# SCH_airocat_2023-06-29.net
KiCad netlist of a schematic drawn in EasyEDA
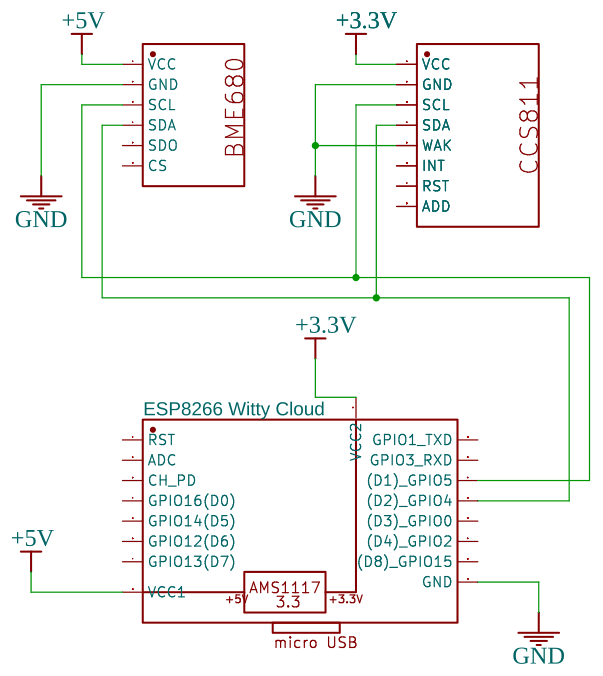
[diagram p0: schematic sheet]

(export (version "E")
  (design (tool "Eeschema 10.0.6"))
  (components
    (comp (ref "U1") (value "BME680") (libsource (lib "") (part "BME680")))
    (comp (ref "U2") (value "CCS811") (libsource (lib "") (part "CCS811")))
    (comp (ref "U3") (value "ESP8266 Witty Cloud") (libsource (lib "") (part "ESP8266 Witty Cloud")))
  )
  (nets
    (net (code "1") (name "+3.3V") (class "Default")
      (node (ref "U2") (pin "1") (pinfunction "VCC_1") (pintype "unspecified"))
      (node (ref "U3") (pin "17") (pinfunction "VCC2_17") (pintype "unspecified"))
    )
    (net (code "2") (name "+5V") (class "Default")
      (node (ref "U1") (pin "1") (pinfunction "VCC_1") (pintype "unspecified"))
      (node (ref "U3") (pin "8") (pinfunction "VCC1_8") (pintype "unspecified"))
    )
    (net (code "3") (name "GND") (class "Default")
      (node (ref "U1") (pin "2") (pinfunction "GND_2") (pintype "unspecified"))
      (node (ref "U2") (pin "2") (pinfunction "GND_2") (pintype "unspecified"))
      (node (ref "U2") (pin "5") (pinfunction "WAK_5") (pintype "unspecified"))
      (node (ref "U3") (pin "9") (pinfunction "GND_9") (pintype "unspecified"))
    )
    (net (code "4") (name "Net-(U1-SCL)") (class "Default")
      (node (ref "U1") (pin "3") (pinfunction "SCL_3") (pintype "unspecified"))
      (node (ref "U2") (pin "3") (pinfunction "SCL_3") (pintype "unspecified"))
      (node (ref "U3") (pin "14") (pinfunction "(D1)_GPIO5_14") (pintype "unspecified"))
    )
    (net (code "5") (name "Net-(U1-SDA)") (class "Default")
      (node (ref "U1") (pin "4") (pinfunction "SDA_4") (pintype "unspecified"))
      (node (ref "U2") (pin "4") (pinfunction "SDA_4") (pintype "unspecified"))
      (node (ref "U3") (pin "13") (pinfunction "(D2)_GPIO4_13") (pintype "unspecified"))
    )
    (net (code "6") (name "unconnected-(U1-CS-Pad6)") (class "Default")
      (node (ref "U1") (pin "6") (pinfunction "CS_6") (pintype "unspecified"))
    )
    (net (code "7") (name "unconnected-(U1-SDO-Pad5)") (class "Default")
      (node (ref "U1") (pin "5") (pinfunction "SDO_5") (pintype "unspecified"))
    )
    (net (code "8") (name "unconnected-(U2-ADD-Pad8)") (class "Default")
      (node (ref "U2") (pin "8") (pinfunction "ADD_8") (pintype "unspecified"))
    )
    (net (code "9") (name "unconnected-(U2-INT-Pad6)") (class "Default")
      (node (ref "U2") (pin "6") (pinfunction "INT_6") (pintype "unspecified"))
    )
    (net (code "10") (name "unconnected-(U2-RST-Pad7)") (class "Default")
      (node (ref "U2") (pin "7") (pinfunction "RST_7") (pintype "unspecified"))
    )
    (net (code "11") (name "unconnected-(U3-(D3)_GPIO0-Pad12)") (class "Default")
      (node (ref "U3") (pin "12") (pinfunction "(D3)_GPIO0_12") (pintype "unspecified"))
    )
    (net (code "12") (name "unconnected-(U3-(D4)_GPIO2-Pad11)") (class "Default")
      (node (ref "U3") (pin "11") (pinfunction "(D4)_GPIO2_11") (pintype "unspecified"))
    )
    (net (code "13") (name "unconnected-(U3-(D8)_GPIO15-Pad10)") (class "Default")
      (node (ref "U3") (pin "10") (pinfunction "(D8)_GPIO15_10") (pintype "unspecified"))
    )
    (net (code "14") (name "unconnected-(U3-ADC-Pad2)") (class "Default")
      (node (ref "U3") (pin "2") (pinfunction "ADC_2") (pintype "unspecified"))
    )
    (net (code "15") (name "unconnected-(U3-CH_PD-Pad3)") (class "Default")
      (node (ref "U3") (pin "3") (pinfunction "CH_PD_3") (pintype "unspecified"))
    )
    (net (code "16") (name "unconnected-(U3-GPIO1_TXD-Pad16)") (class "Default")
      (node (ref "U3") (pin "16") (pinfunction "GPIO1_TXD_16") (pintype "unspecified"))
    )
    (net (code "17") (name "unconnected-(U3-GPIO3_RXD-Pad15)") (class "Default")
      (node (ref "U3") (pin "15") (pinfunction "GPIO3_RXD_15") (pintype "unspecified"))
    )
    (net (code "18") (name "unconnected-(U3-GPIO12(D6)-Pad6)") (class "Default")
      (node (ref "U3") (pin "6") (pinfunction "GPIO12(D6)_6") (pintype "unspecified"))
    )
    (net (code "19") (name "unconnected-(U3-GPIO13(D7)-Pad7)") (class "Default")
      (node (ref "U3") (pin "7") (pinfunction "GPIO13(D7)_7") (pintype "unspecified"))
    )
    (net (code "20") (name "unconnected-(U3-GPIO14(D5)-Pad5)") (class "Default")
      (node (ref "U3") (pin "5") (pinfunction "GPIO14(D5)_5") (pintype "unspecified"))
    )
    (net (code "21") (name "unconnected-(U3-GPIO16(D0)-Pad4)") (class "Default")
      (node (ref "U3") (pin "4") (pinfunction "GPIO16(D0)_4") (pintype "unspecified"))
    )
    (net (code "22") (name "unconnected-(U3-RST-Pad1)") (class "Default")
      (node (ref "U3") (pin "1") (pinfunction "RST_1") (pintype "unspecified"))
    )
  )
)
